# Power_Supply.net
KiCad netlist of a schematic drawn in Altium Designer
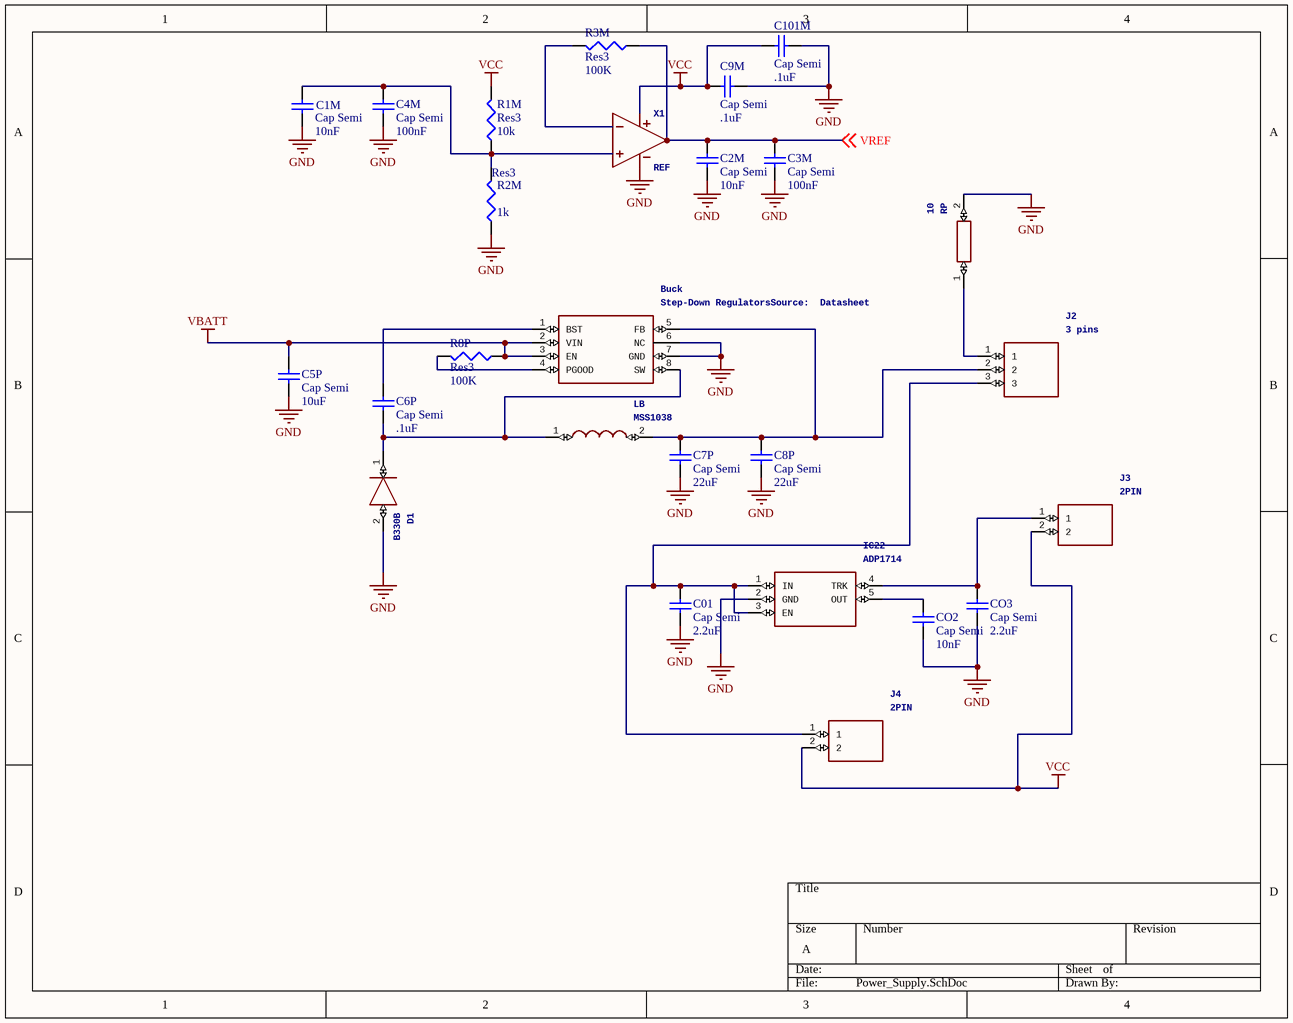
[diagram p0: Power_Supply.SchDoc]

(export (version "E")
  (design (tool "Eeschema 10.0.6"))
  (components
    (comp (ref "10")
      (value "RP")
      (footprint "RESAD3800W75L1600D550")
      (fields
        (field (name "MANUFACTURER_PART_NUMBER") "ROX3SJ220R")
        (field (name "RS_PART_NUMBER") "1615998")
      )
      (libsource (lib "ROX3SJ220R") (part "ROX3SJ220R"))
    )
    (comp (ref "Buck")
      (value "Step-Down RegulatorsSource:  Datasheet")
      (footprint "SOIC127P600X175-9N")
      (fields
        (field (name "MANUFACTURER_PART_NUMBER") "ADP2302ARDZ-5.0-R7")
        (field (name "RS_PART_NUMBER") "7591815P")
      )
      (libsource (lib "ADP2302ARDZ-5") (part "ADP2302ARDZ-5.0-R7"))
    )
    (comp (ref "C01")
      (value "Cap Semi")
      (footprint "1608[0603]")
      (description "Capacitor (Semiconductor SIM Model)")
      (fields (field (name "ALTIUM_VALUE") "2.2uF") (field (name "PUBLISHER") "Altium Limited"))
      (libsource (lib "Miscellaneous Devices") (part "Cap Semi"))
    )
    (comp (ref "C1M")
      (value "Cap Semi")
      (footprint "CAPPM6032X280N")
      (description "Capacitor (Semiconductor SIM Model)")
      (fields (field (name "ALTIUM_VALUE") "10nF") (field (name "PUBLISHER") "Altium Limited"))
      (libsource (lib "Miscellaneous Devices") (part "Cap Semi"))
    )
    (comp (ref "C2M")
      (value "Cap Semi")
      (footprint "CAPPM6032X280N")
      (description "Capacitor (Semiconductor SIM Model)")
      (fields (field (name "ALTIUM_VALUE") "10nF") (field (name "PUBLISHER") "Altium Limited"))
      (libsource (lib "Miscellaneous Devices") (part "Cap Semi"))
    )
    (comp (ref "C3M")
      (value "Cap Semi")
      (footprint "1608[0603]")
      (description "Capacitor (Semiconductor SIM Model)")
      (fields (field (name "ALTIUM_VALUE") "100nF") (field (name "PUBLISHER") "Altium Limited"))
      (libsource (lib "Miscellaneous Devices") (part "Cap Semi"))
    )
    (comp (ref "C4M")
      (value "Cap Semi")
      (footprint "1608[0603]")
      (description "Capacitor (Semiconductor SIM Model)")
      (fields (field (name "ALTIUM_VALUE") "100nF") (field (name "PUBLISHER") "Altium Limited"))
      (libsource (lib "Miscellaneous Devices") (part "Cap Semi"))
    )
    (comp (ref "C5P")
      (value "Cap Semi")
      (footprint "1608[0603]")
      (description "Capacitor (Semiconductor SIM Model)")
      (fields (field (name "ALTIUM_VALUE") "10uF") (field (name "PUBLISHER") "Altium Limited"))
      (libsource (lib "Miscellaneous Devices") (part "Cap Semi"))
    )
    (comp (ref "C6P")
      (value "Cap Semi")
      (footprint "1608[0603]")
      (description "Capacitor (Semiconductor SIM Model)")
      (fields (field (name "ALTIUM_VALUE") ".1uF") (field (name "PUBLISHER") "Altium Limited"))
      (libsource (lib "Miscellaneous Devices") (part "Cap Semi"))
    )
    (comp (ref "C7P")
      (value "Cap Semi")
      (footprint "1608[0603]")
      (description "Capacitor (Semiconductor SIM Model)")
      (fields (field (name "ALTIUM_VALUE") "22uF") (field (name "PUBLISHER") "Altium Limited"))
      (libsource (lib "Miscellaneous Devices") (part "Cap Semi"))
    )
    (comp (ref "C8P")
      (value "Cap Semi")
      (footprint "1608[0603]")
      (description "Capacitor (Semiconductor SIM Model)")
      (fields (field (name "ALTIUM_VALUE") "22uF") (field (name "PUBLISHER") "Altium Limited"))
      (libsource (lib "Miscellaneous Devices") (part "Cap Semi"))
    )
    (comp (ref "C9M")
      (value "Cap Semi")
      (footprint "1608[0603]")
      (description "Capacitor (Semiconductor SIM Model)")
      (fields (field (name "ALTIUM_VALUE") ".1uF") (field (name "PUBLISHER") "Altium Limited"))
      (libsource (lib "Miscellaneous Devices") (part "Cap Semi"))
    )
    (comp (ref "C101M")
      (value "Cap Semi")
      (footprint "CAPPM6032X280N")
      (description "Capacitor (Semiconductor SIM Model)")
      (fields (field (name "ALTIUM_VALUE") ".1uF") (field (name "PUBLISHER") "Altium Limited"))
      (libsource (lib "Miscellaneous Devices") (part "Cap Semi"))
    )
    (comp (ref "CO2")
      (value "Cap Semi")
      (footprint "1608[0603]")
      (description "Capacitor (Semiconductor SIM Model)")
      (fields (field (name "ALTIUM_VALUE") "10nF") (field (name "PUBLISHER") "Altium Limited"))
      (libsource (lib "Miscellaneous Devices") (part "Cap Semi"))
    )
    (comp (ref "CO3")
      (value "Cap Semi")
      (footprint "1608[0603]")
      (description "Capacitor (Semiconductor SIM Model)")
      (fields (field (name "ALTIUM_VALUE") "2.2uF") (field (name "PUBLISHER") "Altium Limited"))
      (libsource (lib "Miscellaneous Devices") (part "Cap Semi"))
    )
    (comp (ref "D1")
      (value "B330B")
      (footprint "DIOM5336X250N")
      (fields
        (field (name "MANUFACTURER_PART_NUMBER") "B330B-13-F")
        (field (name "RS_PART_NUMBER") "9228339")
      )
      (libsource (lib "B330B-13-F") (part "B330B-13-F"))
    )
    (comp (ref "IC22")
      (value "ADP1714")
      (footprint "SOT95P280X100-5N")
      (fields (field (name "MANUFACTURER_PART_NUMBER") "ADP1714AUJZ-3.3-R7"))
      (libsource (lib "ADP1714AUJZ-3") (part "ADP1714AUJZ-3.3-R7"))
    )
    (comp (ref "J2")
      (value "3 pins")
      (footprint "HDRV3W95P0X254_1X3_762X254X869")
      (fields
        (field (name "MANUFACTURER_PART_NUMBER") "61300311121")
        (field (name "RS_PART_NUMBER") "1725145")
      )
      (libsource (lib "61300311121") (part "61300311121"))
    )
    (comp (ref "J3")
      (value "2PIN")
      (footprint "HDRV2W110P0X254_1X2_508X254X85")
      (fields
        (field (name "MANUFACTURER_PART_NUMBER") "61300211121")
        (field (name "RS_PART_NUMBER") "8281581P")
      )
      (libsource (lib "61300211121") (part "61300211121"))
    )
    (comp (ref "J4")
      (value "2PIN")
      (footprint "HDRV2W110P0X254_1X2_508X254X85")
      (fields
        (field (name "MANUFACTURER_PART_NUMBER") "61300211121")
        (field (name "RS_PART_NUMBER") "8281581P")
      )
      (libsource (lib "61300211121") (part "61300211121"))
    )
    (comp (ref "LB")
      (value "MSS1038")
      (footprint "INDM102102X400N")
      (fields (field (name "MANUFACTURER_PART_NUMBER") "MSS1038-183MLB"))
      (libsource (lib "MSS1038-183MLB") (part "MSS1038-183MLB"))
    )
    (comp (ref "R1M")
      (value "Res3")
      (footprint "1608[0603]")
      (description "Resistor")
      (fields (field (name "ALTIUM_VALUE") "10k") (field (name "PUBLISHER") "Altium Limited"))
      (libsource (lib "Miscellaneous Devices") (part "Res3"))
    )
    (comp (ref "R2M")
      (value "Res3")
      (footprint "1608[0603]")
      (description "Resistor")
      (fields (field (name "ALTIUM_VALUE") "1k") (field (name "PUBLISHER") "Altium Limited"))
      (libsource (lib "Miscellaneous Devices") (part "Res3"))
    )
    (comp (ref "R3M")
      (value "Res3")
      (footprint "1608[0603]")
      (description "Resistor")
      (fields (field (name "ALTIUM_VALUE") "100K") (field (name "PUBLISHER") "Altium Limited"))
      (libsource (lib "Miscellaneous Devices") (part "Res3"))
    )
    (comp (ref "R8P")
      (value "Res3")
      (footprint "1608[0603]")
      (description "Resistor")
      (fields (field (name "ALTIUM_VALUE") "100K") (field (name "PUBLISHER") "Altium Limited"))
      (libsource (lib "Miscellaneous Devices") (part "Res3"))
    )
    (comp (ref "X1")
      (value "REF")
      (footprint "SOT95P290X145-5N")
      (fields (field (name "LIBRARYNAME") "Opamps"))
      (libsource (lib "Opamps") (part "OPAMP2"))
    )
  )
  (nets
    (net (code "1") (name "GND") (class "Default")
      (node (ref "10") (pin "2") (pinfunction "2_2") (pintype "bidirectional"))
      (node (ref "Buck") (pin "6") (pinfunction "NC_6") (pintype "passive"))
      (node (ref "Buck") (pin "7") (pinfunction "GND_7") (pintype "bidirectional"))
      (node (ref "C01") (pin "1") (pinfunction "1_1") (pintype "passive"))
      (node (ref "C101M") (pin "1") (pinfunction "1_1") (pintype "passive"))
      (node (ref "C1M") (pin "1") (pinfunction "1_1") (pintype "passive"))
      (node (ref "C2M") (pin "1") (pinfunction "1_1") (pintype "passive"))
      (node (ref "C3M") (pin "1") (pinfunction "1_1") (pintype "passive"))
      (node (ref "C4M") (pin "1") (pinfunction "1_1") (pintype "passive"))
      (node (ref "C5P") (pin "1") (pinfunction "1_1") (pintype "passive"))
      (node (ref "C7P") (pin "1") (pinfunction "1_1") (pintype "passive"))
      (node (ref "C8P") (pin "1") (pinfunction "1_1") (pintype "passive"))
      (node (ref "C9M") (pin "1") (pinfunction "1_1") (pintype "passive"))
      (node (ref "CO2") (pin "1") (pinfunction "1_1") (pintype "passive"))
      (node (ref "CO3") (pin "1") (pinfunction "1_1") (pintype "passive"))
      (node (ref "D1") (pin "2") (pinfunction "A_2") (pintype "bidirectional"))
      (node (ref "IC22") (pin "2") (pinfunction "GND_2") (pintype "bidirectional"))
      (node (ref "R2M") (pin "2") (pinfunction "2_2") (pintype "passive"))
      (node (ref "X1") (pin "2") (pinfunction "V-_2") (pintype "passive"))
    )
    (net (code "2") (name "Net-(10-Pad1)") (class "Default")
      (node (ref "10") (pin "1") (pinfunction "1_1") (pintype "bidirectional"))
      (node (ref "J2") (pin "1") (pinfunction "1_1") (pintype "bidirectional"))
    )
    (net (code "3") (name "Net-(Buck-BST)") (class "Default")
      (node (ref "Buck") (pin "1") (pinfunction "BST_1") (pintype "bidirectional"))
      (node (ref "C6P") (pin "2") (pinfunction "2_2") (pintype "passive"))
    )
    (net (code "4") (name "Net-(Buck-FB)") (class "Default")
      (node (ref "Buck") (pin "5") (pinfunction "FB_5") (pintype "bidirectional"))
      (node (ref "C7P") (pin "2") (pinfunction "2_2") (pintype "passive"))
      (node (ref "C8P") (pin "2") (pinfunction "2_2") (pintype "passive"))
      (node (ref "J2") (pin "2") (pinfunction "2_2") (pintype "bidirectional"))
      (node (ref "LB") (pin "2") (pinfunction "2_2") (pintype "bidirectional"))
    )
    (net (code "5") (name "Net-(Buck-PGOOD)") (class "Default")
      (node (ref "Buck") (pin "4") (pinfunction "PGOOD_4") (pintype "bidirectional"))
      (node (ref "R8P") (pin "1") (pinfunction "1_1") (pintype "passive"))
    )
    (net (code "6") (name "Net-(Buck-SW)") (class "Default")
      (node (ref "Buck") (pin "8") (pinfunction "SW_8") (pintype "bidirectional"))
      (node (ref "C6P") (pin "1") (pinfunction "1_1") (pintype "passive"))
      (node (ref "D1") (pin "1") (pinfunction "K_1") (pintype "bidirectional"))
      (node (ref "LB") (pin "1") (pinfunction "1_1") (pintype "bidirectional"))
    )
    (net (code "7") (name "Net-(IC22-EN)") (class "Default")
      (node (ref "C01") (pin "2") (pinfunction "2_2") (pintype "passive"))
      (node (ref "IC22") (pin "1") (pinfunction "IN_1") (pintype "bidirectional"))
      (node (ref "IC22") (pin "3") (pinfunction "EN_3") (pintype "bidirectional"))
      (node (ref "J2") (pin "3") (pinfunction "3_3") (pintype "bidirectional"))
      (node (ref "J4") (pin "1") (pinfunction "1_1") (pintype "bidirectional"))
    )
    (net (code "8") (name "Net-(IC22-OUT)") (class "Default")
      (node (ref "CO2") (pin "2") (pinfunction "2_2") (pintype "passive"))
      (node (ref "IC22") (pin "5") (pinfunction "OUT_5") (pintype "bidirectional"))
    )
    (net (code "9") (name "Net-(IC22-TRK)") (class "Default")
      (node (ref "CO3") (pin "2") (pinfunction "2_2") (pintype "passive"))
      (node (ref "IC22") (pin "4") (pinfunction "TRK_4") (pintype "bidirectional"))
      (node (ref "J3") (pin "1") (pinfunction "1_1") (pintype "bidirectional"))
    )
    (net (code "10") (name "Net-(X1-IN+)") (class "Default")
      (node (ref "C1M") (pin "2") (pinfunction "2_2") (pintype "passive"))
      (node (ref "C4M") (pin "2") (pinfunction "2_2") (pintype "passive"))
      (node (ref "R1M") (pin "2") (pinfunction "2_2") (pintype "passive"))
      (node (ref "R2M") (pin "1") (pinfunction "1_1") (pintype "passive"))
      (node (ref "X1") (pin "3") (pinfunction "IN+_3") (pintype "passive"))
    )
    (net (code "11") (name "Net-(X1-IN-)") (class "Default")
      (node (ref "R3M") (pin "1") (pinfunction "1_1") (pintype "passive"))
      (node (ref "X1") (pin "4") (pinfunction "IN-_4") (pintype "passive"))
    )
    (net (code "12") (name "VBATT") (class "Default")
      (node (ref "Buck") (pin "2") (pinfunction "VIN_2") (pintype "bidirectional"))
      (node (ref "Buck") (pin "3") (pinfunction "EN_3") (pintype "bidirectional"))
      (node (ref "C5P") (pin "2") (pinfunction "2_2") (pintype "passive"))
      (node (ref "R8P") (pin "2") (pinfunction "2_2") (pintype "passive"))
    )
    (net (code "13") (name "VCC") (class "Default")
      (node (ref "C101M") (pin "2") (pinfunction "2_2") (pintype "passive"))
      (node (ref "C9M") (pin "2") (pinfunction "2_2") (pintype "passive"))
      (node (ref "J3") (pin "2") (pinfunction "2_2") (pintype "bidirectional"))
      (node (ref "J4") (pin "2") (pinfunction "2_2") (pintype "bidirectional"))
      (node (ref "R1M") (pin "1") (pinfunction "1_1") (pintype "passive"))
      (node (ref "X1") (pin "5") (pinfunction "V+_5") (pintype "passive"))
    )
    (net (code "14") (name "VREF") (class "Default")
      (node (ref "C2M") (pin "2") (pinfunction "2_2") (pintype "passive"))
      (node (ref "C3M") (pin "2") (pinfunction "2_2") (pintype "passive"))
      (node (ref "R3M") (pin "2") (pinfunction "2_2") (pintype "passive"))
      (node (ref "X1") (pin "1") (pinfunction "OUT_1") (pintype "passive"))
    )
  )
)
